# pic_can_router.net
KiCad netlist of a schematic drawn in EAGLE
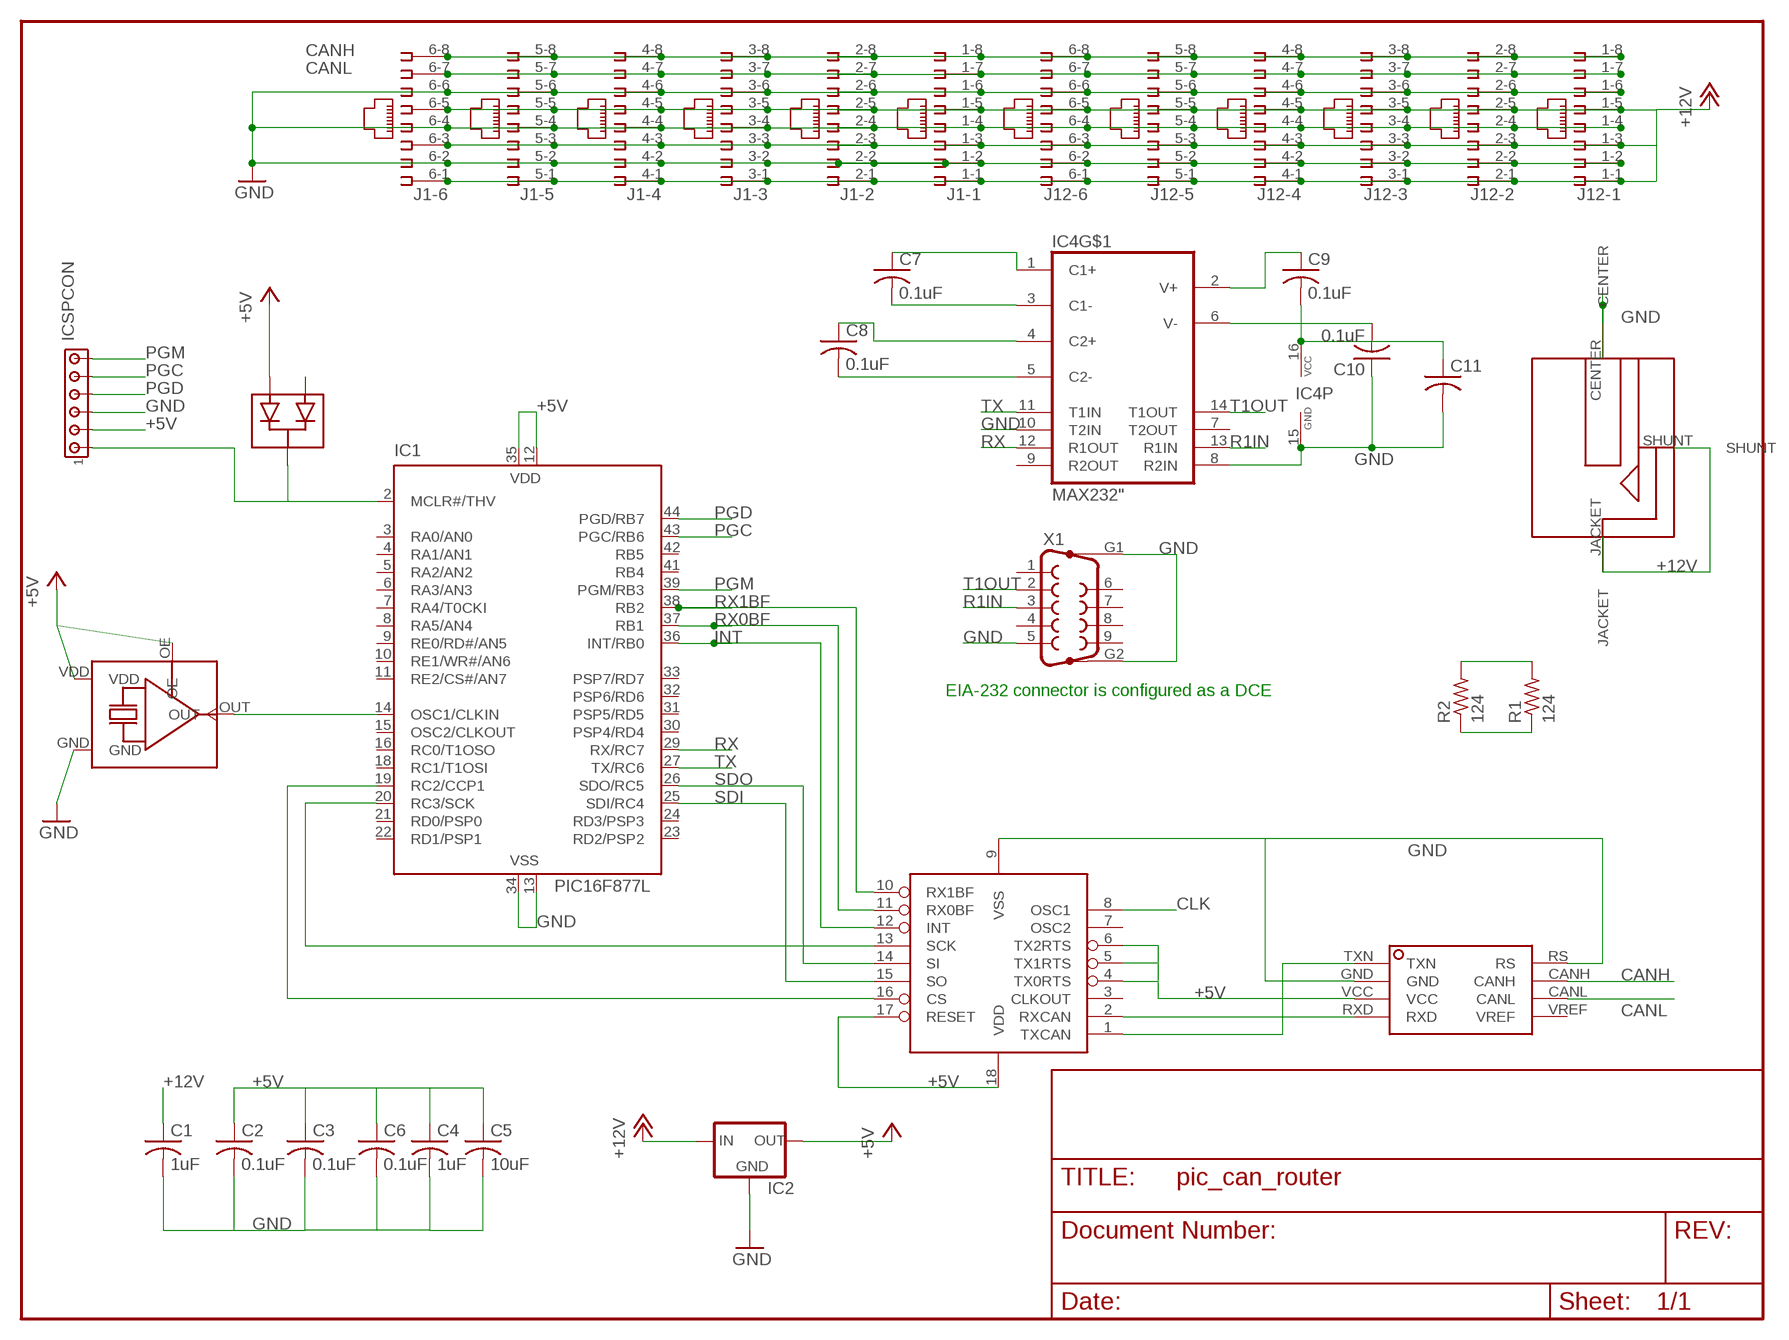
[diagram p0: schematic, sheet 1]

(export (version "E")
  (design (tool "Eeschema 10.0.6"))
  (components
    (comp (ref "C1")
      (value "1uF")
      (footprint "eagle-import:C1206")
      (libsource (lib "eagle-import") (part "C-USC1206"))
    )
    (comp (ref "C2")
      (value "0.1uF")
      (footprint "eagle-import:C0805")
      (libsource (lib "eagle-import") (part "C-USC0805"))
    )
    (comp (ref "C3")
      (value "0.1uF")
      (footprint "eagle-import:C0805")
      (libsource (lib "eagle-import") (part "C-USC0805"))
    )
    (comp (ref "C4")
      (value "1uF")
      (footprint "eagle-import:C1206")
      (libsource (lib "eagle-import") (part "C-USC1206"))
    )
    (comp (ref "C5")
      (value "10uF")
      (footprint "eagle-import:C1210")
      (libsource (lib "eagle-import") (part "C-USC1210"))
    )
    (comp (ref "C6")
      (value "0.1uF")
      (footprint "eagle-import:C0805")
      (libsource (lib "eagle-import") (part "C-USC0805"))
    )
    (comp (ref "C7")
      (value "0.1uF")
      (footprint "eagle-import:C0805")
      (libsource (lib "eagle-import") (part "C-USC0805"))
    )
    (comp (ref "C8")
      (value "0.1uF")
      (footprint "eagle-import:C0805")
      (libsource (lib "eagle-import") (part "C-USC0805"))
    )
    (comp (ref "C9")
      (value "0.1uF")
      (footprint "eagle-import:C0805")
      (libsource (lib "eagle-import") (part "C-USC0805"))
    )
    (comp (ref "C10")
      (value "0.1uF")
      (footprint "eagle-import:C0805")
      (libsource (lib "eagle-import") (part "C-USC0805"))
    )
    (comp (ref "C11")
      (value "C-USC0805")
      (footprint "eagle-import:C0805")
      (libsource (lib "eagle-import") (part "C-USC0805"))
    )
    (comp (ref "IC1")
      (value "PIC16F877L")
      (footprint "eagle-import:PLCC-44")
      (libsource (lib "eagle-import") (part "PIC16F87L7"))
    )
    (comp (ref "IC2")
      (value "78XXL")
      (footprint "eagle-import:78XXL")
      (libsource (lib "eagle-import") (part "78XXL"))
    )
    (comp (ref "IC3")
      (value "UC5350D")
      (footprint "eagle-import:SOIC8")
      (libsource (lib "eagle-import") (part "UC5350D"))
    )
    (comp (ref "IC4")
      (value "MAX232\"")
      (footprint "eagle-import:SO16")
      (libsource (lib "eagle-import") (part "MAX232{dblquote}"))
    )
    (comp (ref "ICSPCON")
      (value "MTA06-100")
      (footprint "eagle-import:10X06MTA")
      (libsource (lib "eagle-import") (part "MTA06-100"))
    )
    (comp (ref "J1")
      (value "557564-1")
      (footprint "eagle-import:557564-1")
      (libsource (lib "eagle-import") (part "557564-1"))
    )
    (comp (ref "J12")
      (value "557564-1")
      (footprint "eagle-import:557564-1")
      (libsource (lib "eagle-import") (part "557564-1"))
    )
    (comp (ref "MCP1")
      (value "MCP2510-I/SO")
      (footprint "eagle-import:SO-18W@1")
      (libsource (lib "eagle-import") (part "MCP2510-I/SO"))
    )
    (comp (ref "R1")
      (value "124")
      (footprint "eagle-import:R0805")
      (libsource (lib "eagle-import") (part "R-US_R0805"))
    )
    (comp (ref "R2")
      (value "124")
      (footprint "eagle-import:R0805")
      (libsource (lib "eagle-import") (part "R-US_R0805"))
    )
    (comp (ref "U$1")
      (value "SG-615P")
      (footprint "eagle-import:SG-615")
      (libsource (lib "eagle-import") (part "SG-615P"))
    )
    (comp (ref "U$2")
      (value "BAV70_")
      (footprint "eagle-import:SOT-23")
      (libsource (lib "eagle-import") (part "BAV70_"))
    )
    (comp (ref "U$3")
      (value "RAPC712\"")
      (footprint "eagle-import:RAPC712")
      (libsource (lib "eagle-import") (part "RAPC712{dblquote}"))
    )
    (comp (ref "X1")
      (value "F09HP")
      (footprint "eagle-import:F09HP")
      (libsource (lib "eagle-import") (part "F09HP"))
    )
  )
  (nets
    (net (code "1") (name "+5V") (class "Default")
      (node (ref "C11") (pin "1") (pinfunction "1_1") (pintype "passive"))
      (node (ref "C2") (pin "1") (pinfunction "1_1") (pintype "passive"))
      (node (ref "C3") (pin "1") (pinfunction "1_1") (pintype "passive"))
      (node (ref "C4") (pin "1") (pinfunction "1_1") (pintype "passive"))
      (node (ref "C5") (pin "1") (pinfunction "1_1") (pintype "passive"))
      (node (ref "C6") (pin "1") (pinfunction "1_1") (pintype "passive"))
      (node (ref "C9") (pin "2") (pinfunction "2_2") (pintype "passive"))
      (node (ref "IC1") (pin "12") (pinfunction "VDD_12") (pintype "power_in"))
      (node (ref "IC1") (pin "35") (pinfunction "VDD_35") (pintype "power_in"))
      (node (ref "IC2") (pin "OUT") (pinfunction "OUT_OUT") (pintype "passive"))
      (node (ref "IC3") (pin "VCC") (pinfunction "VCC_VCC") (pintype "bidirectional"))
      (node (ref "IC4") (pin "16") (pinfunction "VCC_16") (pintype "power_in"))
      (node (ref "ICSPCON") (pin "5") (pinfunction "2_5") (pintype "passive"))
      (node (ref "MCP1") (pin "17") (pinfunction "RESET_17") (pintype "input"))
      (node (ref "MCP1") (pin "18") (pinfunction "VDD_18") (pintype "power_in"))
      (node (ref "MCP1") (pin "4") (pinfunction "TX0RTS_4") (pintype "input"))
      (node (ref "MCP1") (pin "5") (pinfunction "TX1RTS_5") (pintype "input"))
      (node (ref "MCP1") (pin "6") (pinfunction "TX2RTS_6") (pintype "input"))
      (node (ref "U$1") (pin "OE") (pinfunction "OE_OE") (pintype "input"))
      (node (ref "U$1") (pin "VDD") (pinfunction "VDD_VDD") (pintype "power_in"))
      (node (ref "U$2") (pin "2") (pinfunction "A2_2") (pintype "bidirectional"))
    )
    (net (code "2") (name "+12V") (class "Default")
      (node (ref "C1") (pin "1") (pinfunction "1_1") (pintype "passive"))
      (node (ref "IC2") (pin "IN") (pinfunction "IN_IN") (pintype "input"))
      (node (ref "J1") (pin "1-1") (pinfunction "1_1-1") (pintype "passive"))
      (node (ref "J1") (pin "1-3") (pinfunction "3_1-3") (pintype "passive"))
      (node (ref "J1") (pin "1-5") (pinfunction "5_1-5") (pintype "passive"))
      (node (ref "J1") (pin "2-1") (pinfunction "1_2-1") (pintype "passive"))
      (node (ref "J1") (pin "2-3") (pinfunction "3_2-3") (pintype "passive"))
      (node (ref "J1") (pin "2-5") (pinfunction "5_2-5") (pintype "passive"))
      (node (ref "J1") (pin "3-1") (pinfunction "1_3-1") (pintype "passive"))
      (node (ref "J1") (pin "3-3") (pinfunction "3_3-3") (pintype "passive"))
      (node (ref "J1") (pin "3-5") (pinfunction "5_3-5") (pintype "passive"))
      (node (ref "J1") (pin "4-1") (pinfunction "1_4-1") (pintype "passive"))
      (node (ref "J1") (pin "4-3") (pinfunction "3_4-3") (pintype "passive"))
      (node (ref "J1") (pin "4-5") (pinfunction "5_4-5") (pintype "passive"))
      (node (ref "J1") (pin "5-1") (pinfunction "1_5-1") (pintype "passive"))
      (node (ref "J1") (pin "5-3") (pinfunction "3_5-3") (pintype "passive"))
      (node (ref "J1") (pin "5-5") (pinfunction "5_5-5") (pintype "passive"))
      (node (ref "J1") (pin "6-1") (pinfunction "1_6-1") (pintype "passive"))
      (node (ref "J1") (pin "6-3") (pinfunction "3_6-3") (pintype "passive"))
      (node (ref "J1") (pin "6-5") (pinfunction "5_6-5") (pintype "passive"))
      (node (ref "J12") (pin "1-1") (pinfunction "1_1-1") (pintype "passive"))
      (node (ref "J12") (pin "1-3") (pinfunction "3_1-3") (pintype "passive"))
      (node (ref "J12") (pin "1-5") (pinfunction "5_1-5") (pintype "passive"))
      (node (ref "J12") (pin "2-1") (pinfunction "1_2-1") (pintype "passive"))
      (node (ref "J12") (pin "2-3") (pinfunction "3_2-3") (pintype "passive"))
      (node (ref "J12") (pin "2-5") (pinfunction "5_2-5") (pintype "passive"))
      (node (ref "J12") (pin "3-1") (pinfunction "1_3-1") (pintype "passive"))
      (node (ref "J12") (pin "3-3") (pinfunction "3_3-3") (pintype "passive"))
      (node (ref "J12") (pin "3-5") (pinfunction "5_3-5") (pintype "passive"))
      (node (ref "J12") (pin "4-1") (pinfunction "1_4-1") (pintype "passive"))
      (node (ref "J12") (pin "4-3") (pinfunction "3_4-3") (pintype "passive"))
      (node (ref "J12") (pin "4-5") (pinfunction "5_4-5") (pintype "passive"))
      (node (ref "J12") (pin "5-1") (pinfunction "1_5-1") (pintype "passive"))
      (node (ref "J12") (pin "5-3") (pinfunction "3_5-3") (pintype "passive"))
      (node (ref "J12") (pin "5-5") (pinfunction "5_5-5") (pintype "passive"))
      (node (ref "J12") (pin "6-1") (pinfunction "1_6-1") (pintype "passive"))
      (node (ref "J12") (pin "6-3") (pinfunction "3_6-3") (pintype "passive"))
      (node (ref "J12") (pin "6-5") (pinfunction "5_6-5") (pintype "passive"))
      (node (ref "U$3") (pin "JACKET") (pinfunction "JACKET_JACKET") (pintype "bidirectional"))
      (node (ref "U$3") (pin "SHUNT") (pinfunction "SHUNT_SHUNT") (pintype "bidirectional"))
    )
    (net (code "3") (name "/CANH") (class "Default")
      (node (ref "IC3") (pin "CANH") (pinfunction "CANH_CANH") (pintype "bidirectional"))
      (node (ref "J1") (pin "1-8") (pinfunction "8_1-8") (pintype "passive"))
      (node (ref "J1") (pin "2-8") (pinfunction "8_2-8") (pintype "passive"))
      (node (ref "J1") (pin "3-8") (pinfunction "8_3-8") (pintype "passive"))
      (node (ref "J1") (pin "4-8") (pinfunction "8_4-8") (pintype "passive"))
      (node (ref "J1") (pin "5-8") (pinfunction "8_5-8") (pintype "passive"))
      (node (ref "J1") (pin "6-8") (pinfunction "8_6-8") (pintype "passive"))
      (node (ref "J12") (pin "1-8") (pinfunction "8_1-8") (pintype "passive"))
      (node (ref "J12") (pin "2-8") (pinfunction "8_2-8") (pintype "passive"))
      (node (ref "J12") (pin "3-8") (pinfunction "8_3-8") (pintype "passive"))
      (node (ref "J12") (pin "4-8") (pinfunction "8_4-8") (pintype "passive"))
      (node (ref "J12") (pin "5-8") (pinfunction "8_5-8") (pintype "passive"))
      (node (ref "J12") (pin "6-8") (pinfunction "8_6-8") (pintype "passive"))
      (node (ref "R1") (pin "2") (pinfunction "2_2") (pintype "passive"))
      (node (ref "R2") (pin "2") (pinfunction "2_2") (pintype "passive"))
    )
    (net (code "4") (name "/CANL") (class "Default")
      (node (ref "IC3") (pin "CANL") (pinfunction "CANL_CANL") (pintype "bidirectional"))
      (node (ref "J1") (pin "1-7") (pinfunction "7_1-7") (pintype "passive"))
      (node (ref "J1") (pin "2-7") (pinfunction "7_2-7") (pintype "passive"))
      (node (ref "J1") (pin "3-7") (pinfunction "7_3-7") (pintype "passive"))
      (node (ref "J1") (pin "4-7") (pinfunction "7_4-7") (pintype "passive"))
      (node (ref "J1") (pin "5-7") (pinfunction "7_5-7") (pintype "passive"))
      (node (ref "J1") (pin "6-7") (pinfunction "7_6-7") (pintype "passive"))
      (node (ref "J12") (pin "1-7") (pinfunction "7_1-7") (pintype "passive"))
      (node (ref "J12") (pin "2-7") (pinfunction "7_2-7") (pintype "passive"))
      (node (ref "J12") (pin "3-7") (pinfunction "7_3-7") (pintype "passive"))
      (node (ref "J12") (pin "4-7") (pinfunction "7_4-7") (pintype "passive"))
      (node (ref "J12") (pin "5-7") (pinfunction "7_5-7") (pintype "passive"))
      (node (ref "J12") (pin "6-7") (pinfunction "7_6-7") (pintype "passive"))
      (node (ref "R1") (pin "1") (pinfunction "1_1") (pintype "passive"))
      (node (ref "R2") (pin "1") (pinfunction "1_1") (pintype "passive"))
    )
    (net (code "5") (name "/CLK") (class "Default")
      (node (ref "IC1") (pin "14") (pinfunction "OSC1/CLKIN_14") (pintype "input"))
      (node (ref "MCP1") (pin "8") (pinfunction "OSC1_8") (pintype "input"))
      (node (ref "U$1") (pin "OUT") (pinfunction "OUT_OUT") (pintype "bidirectional"))
    )
    (net (code "6") (name "/INT") (class "Default")
      (node (ref "IC1") (pin "36") (pinfunction "INT/RB0_36") (pintype "bidirectional"))
      (node (ref "MCP1") (pin "12") (pinfunction "INT_12") (pintype "output"))
    )
    (net (code "7") (name "/PGC") (class "Default")
      (node (ref "IC1") (pin "43") (pinfunction "PGC/RB6_43") (pintype "bidirectional"))
      (node (ref "ICSPCON") (pin "2") (pinfunction "5_2") (pintype "passive"))
    )
    (net (code "8") (name "/PGD") (class "Default")
      (node (ref "IC1") (pin "44") (pinfunction "PGD/RB7_44") (pintype "bidirectional"))
      (node (ref "ICSPCON") (pin "3") (pinfunction "4_3") (pintype "passive"))
    )
    (net (code "9") (name "/PGM") (class "Default")
      (node (ref "IC1") (pin "39") (pinfunction "PGM/RB3_39") (pintype "bidirectional"))
      (node (ref "ICSPCON") (pin "1") (pinfunction "6_1") (pintype "passive"))
    )
    (net (code "10") (name "/R1IN") (class "Default")
      (node (ref "IC4") (pin "13") (pinfunction "R1IN_13") (pintype "input"))
      (node (ref "X1") (pin "3") (pinfunction "3_3") (pintype "passive"))
    )
    (net (code "11") (name "/RX") (class "Default")
      (node (ref "IC1") (pin "29") (pinfunction "RX/RC7_29") (pintype "bidirectional"))
      (node (ref "IC4") (pin "12") (pinfunction "R1OUT_12") (pintype "output"))
    )
    (net (code "12") (name "/RX0BF") (class "Default")
      (node (ref "IC1") (pin "37") (pinfunction "RB1_37") (pintype "bidirectional"))
      (node (ref "MCP1") (pin "11") (pinfunction "RX0BF_11") (pintype "output"))
    )
    (net (code "13") (name "/RX1BF") (class "Default")
      (node (ref "IC1") (pin "38") (pinfunction "RB2_38") (pintype "bidirectional"))
      (node (ref "MCP1") (pin "10") (pinfunction "RX1BF_10") (pintype "output"))
    )
    (net (code "14") (name "/SDI") (class "Default")
      (node (ref "IC1") (pin "25") (pinfunction "SDI/RC4_25") (pintype "bidirectional"))
      (node (ref "MCP1") (pin "15") (pinfunction "SO_15") (pintype "output"))
    )
    (net (code "15") (name "/SDO") (class "Default")
      (node (ref "IC1") (pin "26") (pinfunction "SDO/RC5_26") (pintype "bidirectional"))
      (node (ref "MCP1") (pin "14") (pinfunction "SI_14") (pintype "input"))
    )
    (net (code "16") (name "/T1OUT") (class "Default")
      (node (ref "IC4") (pin "14") (pinfunction "T1OUT_14") (pintype "output"))
      (node (ref "X1") (pin "2") (pinfunction "2_2") (pintype "passive"))
    )
    (net (code "17") (name "/TX") (class "Default")
      (node (ref "IC1") (pin "27") (pinfunction "TX/RC6_27") (pintype "bidirectional"))
      (node (ref "IC4") (pin "11") (pinfunction "T1IN_11") (pintype "input"))
    )
    (net (code "18") (name "GND") (class "Default")
      (node (ref "C1") (pin "2") (pinfunction "2_2") (pintype "passive"))
      (node (ref "C10") (pin "1") (pinfunction "1_1") (pintype "passive"))
      (node (ref "C11") (pin "2") (pinfunction "2_2") (pintype "passive"))
      (node (ref "C2") (pin "2") (pinfunction "2_2") (pintype "passive"))
      (node (ref "C3") (pin "2") (pinfunction "2_2") (pintype "passive"))
      (node (ref "C4") (pin "2") (pinfunction "2_2") (pintype "passive"))
      (node (ref "C5") (pin "2") (pinfunction "2_2") (pintype "passive"))
      (node (ref "C6") (pin "2") (pinfunction "2_2") (pintype "passive"))
      (node (ref "IC1") (pin "13") (pinfunction "VSS_13") (pintype "power_in"))
      (node (ref "IC1") (pin "34") (pinfunction "VSS_34") (pintype "power_in"))
      (node (ref "IC2") (pin "GND") (pinfunction "GND_GND") (pintype "input"))
      (node (ref "IC3") (pin "GND") (pinfunction "GND_GND") (pintype "bidirectional"))
      (node (ref "IC3") (pin "RS") (pinfunction "RS_RS") (pintype "bidirectional"))
      (node (ref "IC4") (pin "10") (pinfunction "T2IN_10") (pintype "input"))
      (node (ref "IC4") (pin "15") (pinfunction "GND_15") (pintype "power_in"))
      (node (ref "IC4") (pin "8") (pinfunction "R2IN_8") (pintype "input"))
      (node (ref "ICSPCON") (pin "4") (pinfunction "3_4") (pintype "passive"))
      (node (ref "J1") (pin "1-2") (pinfunction "2_1-2") (pintype "passive"))
      (node (ref "J1") (pin "1-4") (pinfunction "4_1-4") (pintype "passive"))
      (node (ref "J1") (pin "1-6") (pinfunction "6_1-6") (pintype "passive"))
      (node (ref "J1") (pin "2-2") (pinfunction "2_2-2") (pintype "passive"))
      (node (ref "J1") (pin "2-4") (pinfunction "4_2-4") (pintype "passive"))
      (node (ref "J1") (pin "2-6") (pinfunction "6_2-6") (pintype "passive"))
      (node (ref "J1") (pin "3-2") (pinfunction "2_3-2") (pintype "passive"))
      (node (ref "J1") (pin "3-4") (pinfunction "4_3-4") (pintype "passive"))
      (node (ref "J1") (pin "3-6") (pinfunction "6_3-6") (pintype "passive"))
      (node (ref "J1") (pin "4-2") (pinfunction "2_4-2") (pintype "passive"))
      (node (ref "J1") (pin "4-4") (pinfunction "4_4-4") (pintype "passive"))
      (node (ref "J1") (pin "4-6") (pinfunction "6_4-6") (pintype "passive"))
      (node (ref "J1") (pin "5-2") (pinfunction "2_5-2") (pintype "passive"))
      (node (ref "J1") (pin "5-4") (pinfunction "4_5-4") (pintype "passive"))
      (node (ref "J1") (pin "5-6") (pinfunction "6_5-6") (pintype "passive"))
      (node (ref "J1") (pin "6-2") (pinfunction "2_6-2") (pintype "passive"))
      (node (ref "J1") (pin "6-4") (pinfunction "4_6-4") (pintype "passive"))
      (node (ref "J1") (pin "6-6") (pinfunction "6_6-6") (pintype "passive"))
      (node (ref "J12") (pin "1-2") (pinfunction "2_1-2") (pintype "passive"))
      (node (ref "J12") (pin "1-4") (pinfunction "4_1-4") (pintype "passive"))
      (node (ref "J12") (pin "1-6") (pinfunction "6_1-6") (pintype "passive"))
      (node (ref "J12") (pin "2-2") (pinfunction "2_2-2") (pintype "passive"))
      (node (ref "J12") (pin "2-4") (pinfunction "4_2-4") (pintype "passive"))
      (node (ref "J12") (pin "2-6") (pinfunction "6_2-6") (pintype "passive"))
      (node (ref "J12") (pin "3-2") (pinfunction "2_3-2") (pintype "passive"))
      (node (ref "J12") (pin "3-4") (pinfunction "4_3-4") (pintype "passive"))
      (node (ref "J12") (pin "3-6") (pinfunction "6_3-6") (pintype "passive"))
      (node (ref "J12") (pin "4-2") (pinfunction "2_4-2") (pintype "passive"))
      (node (ref "J12") (pin "4-4") (pinfunction "4_4-4") (pintype "passive"))
      (node (ref "J12") (pin "4-6") (pinfunction "6_4-6") (pintype "passive"))
      (node (ref "J12") (pin "5-2") (pinfunction "2_5-2") (pintype "passive"))
      (node (ref "J12") (pin "5-4") (pinfunction "4_5-4") (pintype "passive"))
      (node (ref "J12") (pin "5-6") (pinfunction "6_5-6") (pintype "passive"))
      (node (ref "J12") (pin "6-2") (pinfunction "2_6-2") (pintype "passive"))
      (node (ref "J12") (pin "6-4") (pinfunction "4_6-4") (pintype "passive"))
      (node (ref "J12") (pin "6-6") (pinfunction "6_6-6") (pintype "passive"))
      (node (ref "MCP1") (pin "9") (pinfunction "VSS_9") (pintype "power_in"))
      (node (ref "U$1") (pin "GND") (pinfunction "GND_GND") (pintype "power_in"))
      (node (ref "U$3") (pin "CENTER") (pinfunction "CENTER_CENTER") (pintype "bidirectional"))
      (node (ref "X1") (pin "5") (pinfunction "5_5") (pintype "passive"))
      (node (ref "X1") (pin "G1") (pinfunction "G1_G1") (pintype "passive"))
      (node (ref "X1") (pin "G2") (pinfunction "G2_G2") (pintype "passive"))
    )
    (net (code "19") (name "Net-(IC1-MCLR#{slash}THV)") (class "Default")
      (node (ref "IC1") (pin "2") (pinfunction "MCLR#/THV_2") (pintype "input"))
      (node (ref "ICSPCON") (pin "6") (pinfunction "1_6") (pintype "passive"))
      (node (ref "U$2") (pin "3") (pinfunction "C_3") (pintype "bidirectional"))
    )
    (net (code "20") (name "Net-(IC1-RC2{slash}CCP1)") (class "Default")
      (node (ref "IC1") (pin "19") (pinfunction "RC2/CCP1_19") (pintype "bidirectional"))
      (node (ref "MCP1") (pin "16") (pinfunction "CS_16") (pintype "input"))
    )
    (net (code "21") (name "Net-(IC1-RC3{slash}SCK)") (class "Default")
      (node (ref "IC1") (pin "20") (pinfunction "RC3/SCK_20") (pintype "bidirectional"))
      (node (ref "MCP1") (pin "13") (pinfunction "SCK_13") (pintype "input"))
    )
    (net (code "22") (name "Net-(IC4A-C1+)") (class "Default")
      (node (ref "C7") (pin "1") (pinfunction "1_1") (pintype "passive"))
      (node (ref "IC4") (pin "1") (pinfunction "C1+_1") (pintype "bidirectional"))
    )
    (net (code "23") (name "Net-(IC4A-C1-)") (class "Default")
      (node (ref "C7") (pin "2") (pinfunction "2_2") (pintype "passive"))
      (node (ref "IC4") (pin "3") (pinfunction "C1-_3") (pintype "bidirectional"))
    )
    (net (code "24") (name "Net-(IC4A-C2+)") (class "Default")
      (node (ref "C8") (pin "1") (pinfunction "1_1") (pintype "passive"))
      (node (ref "IC4") (pin "4") (pinfunction "C2+_4") (pintype "bidirectional"))
    )
    (net (code "25") (name "Net-(IC4A-C2-)") (class "Default")
      (node (ref "C8") (pin "2") (pinfunction "2_2") (pintype "passive"))
      (node (ref "IC4") (pin "5") (pinfunction "C2-_5") (pintype "bidirectional"))
    )
    (net (code "26") (name "Net-(IC4A-V+)") (class "Default")
      (node (ref "C9") (pin "1") (pinfunction "1_1") (pintype "passive"))
      (node (ref "IC4") (pin "2") (pinfunction "V+_2") (pintype "bidirectional"))
    )
    (net (code "27") (name "Net-(IC4A-V-)") (class "Default")
      (node (ref "C10") (pin "2") (pinfunction "2_2") (pintype "passive"))
      (node (ref "IC4") (pin "6") (pinfunction "V-_6") (pintype "bidirectional"))
    )
    (net (code "28") (name "Net-(MCP1-RXCAN)") (class "Default")
      (node (ref "IC3") (pin "RXD") (pinfunction "RXD_RXD") (pintype "bidirectional"))
      (node (ref "MCP1") (pin "2") (pinfunction "RXCAN_2") (pintype "input"))
    )
    (net (code "29") (name "Net-(MCP1-TXCAN)") (class "Default")
      (node (ref "IC3") (pin "TXN") (pinfunction "TXN_TXN") (pintype "bidirectional"))
      (node (ref "MCP1") (pin "1") (pinfunction "TXCAN_1") (pintype "output"))
    )
    (net (code "30") (name "unconnected-(IC1-OSC2{slash}CLKOUT-Pad15)") (class "Default")
      (node (ref "IC1") (pin "15") (pinfunction "OSC2/CLKOUT_15") (pintype "output"))
    )
    (net (code "31") (name "unconnected-(IC1-PSP4{slash}RD4-Pad30)") (class "Default")
      (node (ref "IC1") (pin "30") (pinfunction "PSP4/RD4_30") (pintype "bidirectional"))
    )
    (net (code "32") (name "unconnected-(IC1-PSP5{slash}RD5-Pad31)") (class "Default")
      (node (ref "IC1") (pin "31") (pinfunction "PSP5/RD5_31") (pintype "bidirectional"))
    )
    (net (code "33") (name "unconnected-(IC1-PSP6{slash}RD6-Pad32)") (class "Default")
      (node (ref "IC1") (pin "32") (pinfunction "PSP6/RD6_32") (pintype "bidirectional"))
    )
    (net (code "34") (name "unconnected-(IC1-PSP7{slash}RD7-Pad33)") (class "Default")
      (node (ref "IC1") (pin "33") (pinfunction "PSP7/RD7_33") (pintype "bidirectional"))
    )
    (net (code "35") (name "unconnected-(IC1-RA0{slash}AN0-Pad3)") (class "Default")
      (node (ref "IC1") (pin "3") (pinfunction "RA0/AN0_3") (pintype "bidirectional"))
    )
    (net (code "36") (name "unconnected-(IC1-RA1{slash}AN1-Pad4)") (class "Default")
      (node (ref "IC1") (pin "4") (pinfunction "RA1/AN1_4") (pintype "bidirectional"))
    )
    (net (code "37") (name "unconnected-(IC1-RA2{slash}AN2-Pad5)") (class "Default")
      (node (ref "IC1") (pin "5") (pinfunction "RA2/AN2_5") (pintype "bidirectional"))
    )
    (net (code "38") (name "unconnected-(IC1-RA3{slash}AN3-Pad6)") (class "Default")
      (node (ref "IC1") (pin "6") (pinfunction "RA3/AN3_6") (pintype "bidirectional"))
    )
    (net (code "39") (name "unconnected-(IC1-RA4{slash}T0CKI-Pad7)") (class "Default")
      (node (ref "IC1") (pin "7") (pinfunction "RA4/T0CKI_7") (pintype "bidirectional"))
    )
    (net (code "40") (name "unconnected-(IC1-RA5{slash}AN4-Pad8)") (class "Default")
      (node (ref "IC1") (pin "8") (pinfunction "RA5/AN4_8") (pintype "bidirectional"))
    )
    (net (code "41") (name "unconnected-(IC1-RB4-Pad41)") (class "Default")
      (node (ref "IC1") (pin "41") (pinfunction "RB4_41") (pintype "bidirectional"))
    )
    (net (code "42") (name "unconnected-(IC1-RB5-Pad42)") (class "Default")
      (node (ref "IC1") (pin "42") (pinfunction "RB5_42") (pintype "bidirectional"))
    )
    (net (code "43") (name "unconnected-(IC1-RC0{slash}T1OSO-Pad16)") (class "Default")
      (node (ref "IC1") (pin "16") (pinfunction "RC0/T1OSO_16") (pintype "bidirectional"))
    )
    (net (code "44") (name "unconnected-(IC1-RC1{slash}T1OSI-Pad18)") (class "Default")
      (node (ref "IC1") (pin "18") (pinfunction "RC1/T1OSI_18") (pintype "bidirectional"))
    )
    (net (code "45") (name "unconnected-(IC1-RD0{slash}PSP0-Pad21)") (class "Default")
      (node (ref "IC1") (pin "21") (pinfunction "RD0/PSP0_21") (pintype "bidirectional"))
    )
    (net (code "46") (name "unconnected-(IC1-RD1{slash}PSP1-Pad22)") (class "Default")
      (node (ref "IC1") (pin "22") (pinfunction "RD1/PSP1_22") (pintype "bidirectional"))
    )
    (net (code "47") (name "unconnected-(IC1-RD2{slash}PSP2-Pad23)") (class "Default")
      (node (ref "IC1") (pin "23") (pinfunction "RD2/PSP2_23") (pintype "bidirectional"))
    )
    (net (code "48") (name "unconnected-(IC1-RD3{slash}PSP3-Pad24)") (class "Default")
      (node (ref "IC1") (pin "24") (pinfunction "RD3/PSP3_24") (pintype "bidirectional"))
    )
    (net (code "49") (name "unconnected-(IC1-RE0{slash}RD#{slash}AN5-Pad9)") (class "Default")
      (node (ref "IC1") (pin "9") (pinfunction "RE0/RD#/AN5_9") (pintype "bidirectional"))
    )
    (net (code "50") (name "unconnected-(IC1-RE1{slash}WR#{slash}AN6-Pad10)") (class "Default")
      (node (ref "IC1") (pin "10") (pinfunction "RE1/WR#/AN6_10") (pintype "bidirectional"))
    )
    (net (code "51") (name "unconnected-(IC1-RE2{slash}CS#{slash}AN7-Pad11)") (class "Default")
      (node (ref "IC1") (pin "11") (pinfunction "RE2/CS#/AN7_11") (pintype "bidirectional"))
    )
    (net (code "52") (name "unconnected-(IC3-PadVREF)") (class "Default")
      (node (ref "IC3") (pin "VREF") (pinfunction "VREF_VREF") (pintype "bidirectional"))
    )
    (net (code "53") (name "unconnected-(IC4A-R2OUT-Pad9)") (class "Default")
      (node (ref "IC4") (pin "9") (pinfunction "R2OUT_9") (pintype "output"))
    )
    (net (code "54") (name "unconnected-(IC4A-T2OUT-Pad7)") (class "Default")
      (node (ref "IC4") (pin "7") (pinfunction "T2OUT_7") (pintype "output"))
    )
    (net (code "55") (name "unconnected-(MCP1-CLKOUT-Pad3)") (class "Default")
      (node (ref "MCP1") (pin "3") (pinfunction "CLKOUT_3") (pintype "output"))
    )
    (net (code "56") (name "unconnected-(MCP1-OSC2-Pad7)") (class "Default")
      (node (ref "MCP1") (pin "7") (pinfunction "OSC2_7") (pintype "output"))
    )
    (net (code "57") (name "unconnected-(U$2-A1-Pad1)") (class "Default")
      (node (ref "U$2") (pin "1") (pinfunction "A1_1") (pintype "bidirectional"))
    )
    (net (code "58") (name "unconnected-(X1-Pad1)") (class "Default")
      (node (ref "X1") (pin "1") (pinfunction "1_1") (pintype "passive"))
    )
    (net (code "59") (name "unconnected-(X1-Pad4)") (class "Default")
      (node (ref "X1") (pin "4") (pinfunction "4_4") (pintype "passive"))
    )
    (net (code "60") (name "unconnected-(X1-Pad6)") (class "Default")
      (node (ref "X1") (pin "6") (pinfunction "6_6") (pintype "passive"))
    )
    (net (code "61") (name "unconnected-(X1-Pad7)") (class "Default")
      (node (ref "X1") (pin "7") (pinfunction "7_7") (pintype "passive"))
    )
    (net (code "62") (name "unconnected-(X1-Pad8)") (class "Default")
      (node (ref "X1") (pin "8") (pinfunction "8_8") (pintype "passive"))
    )
    (net (code "63") (name "unconnected-(X1-Pad9)") (class "Default")
      (node (ref "X1") (pin "9") (pinfunction "9_9") (pintype "passive"))
    )
  )
)
